# pca10040_sheet4_connectors.net
KiCad netlist of a schematic drawn in Altium Designer
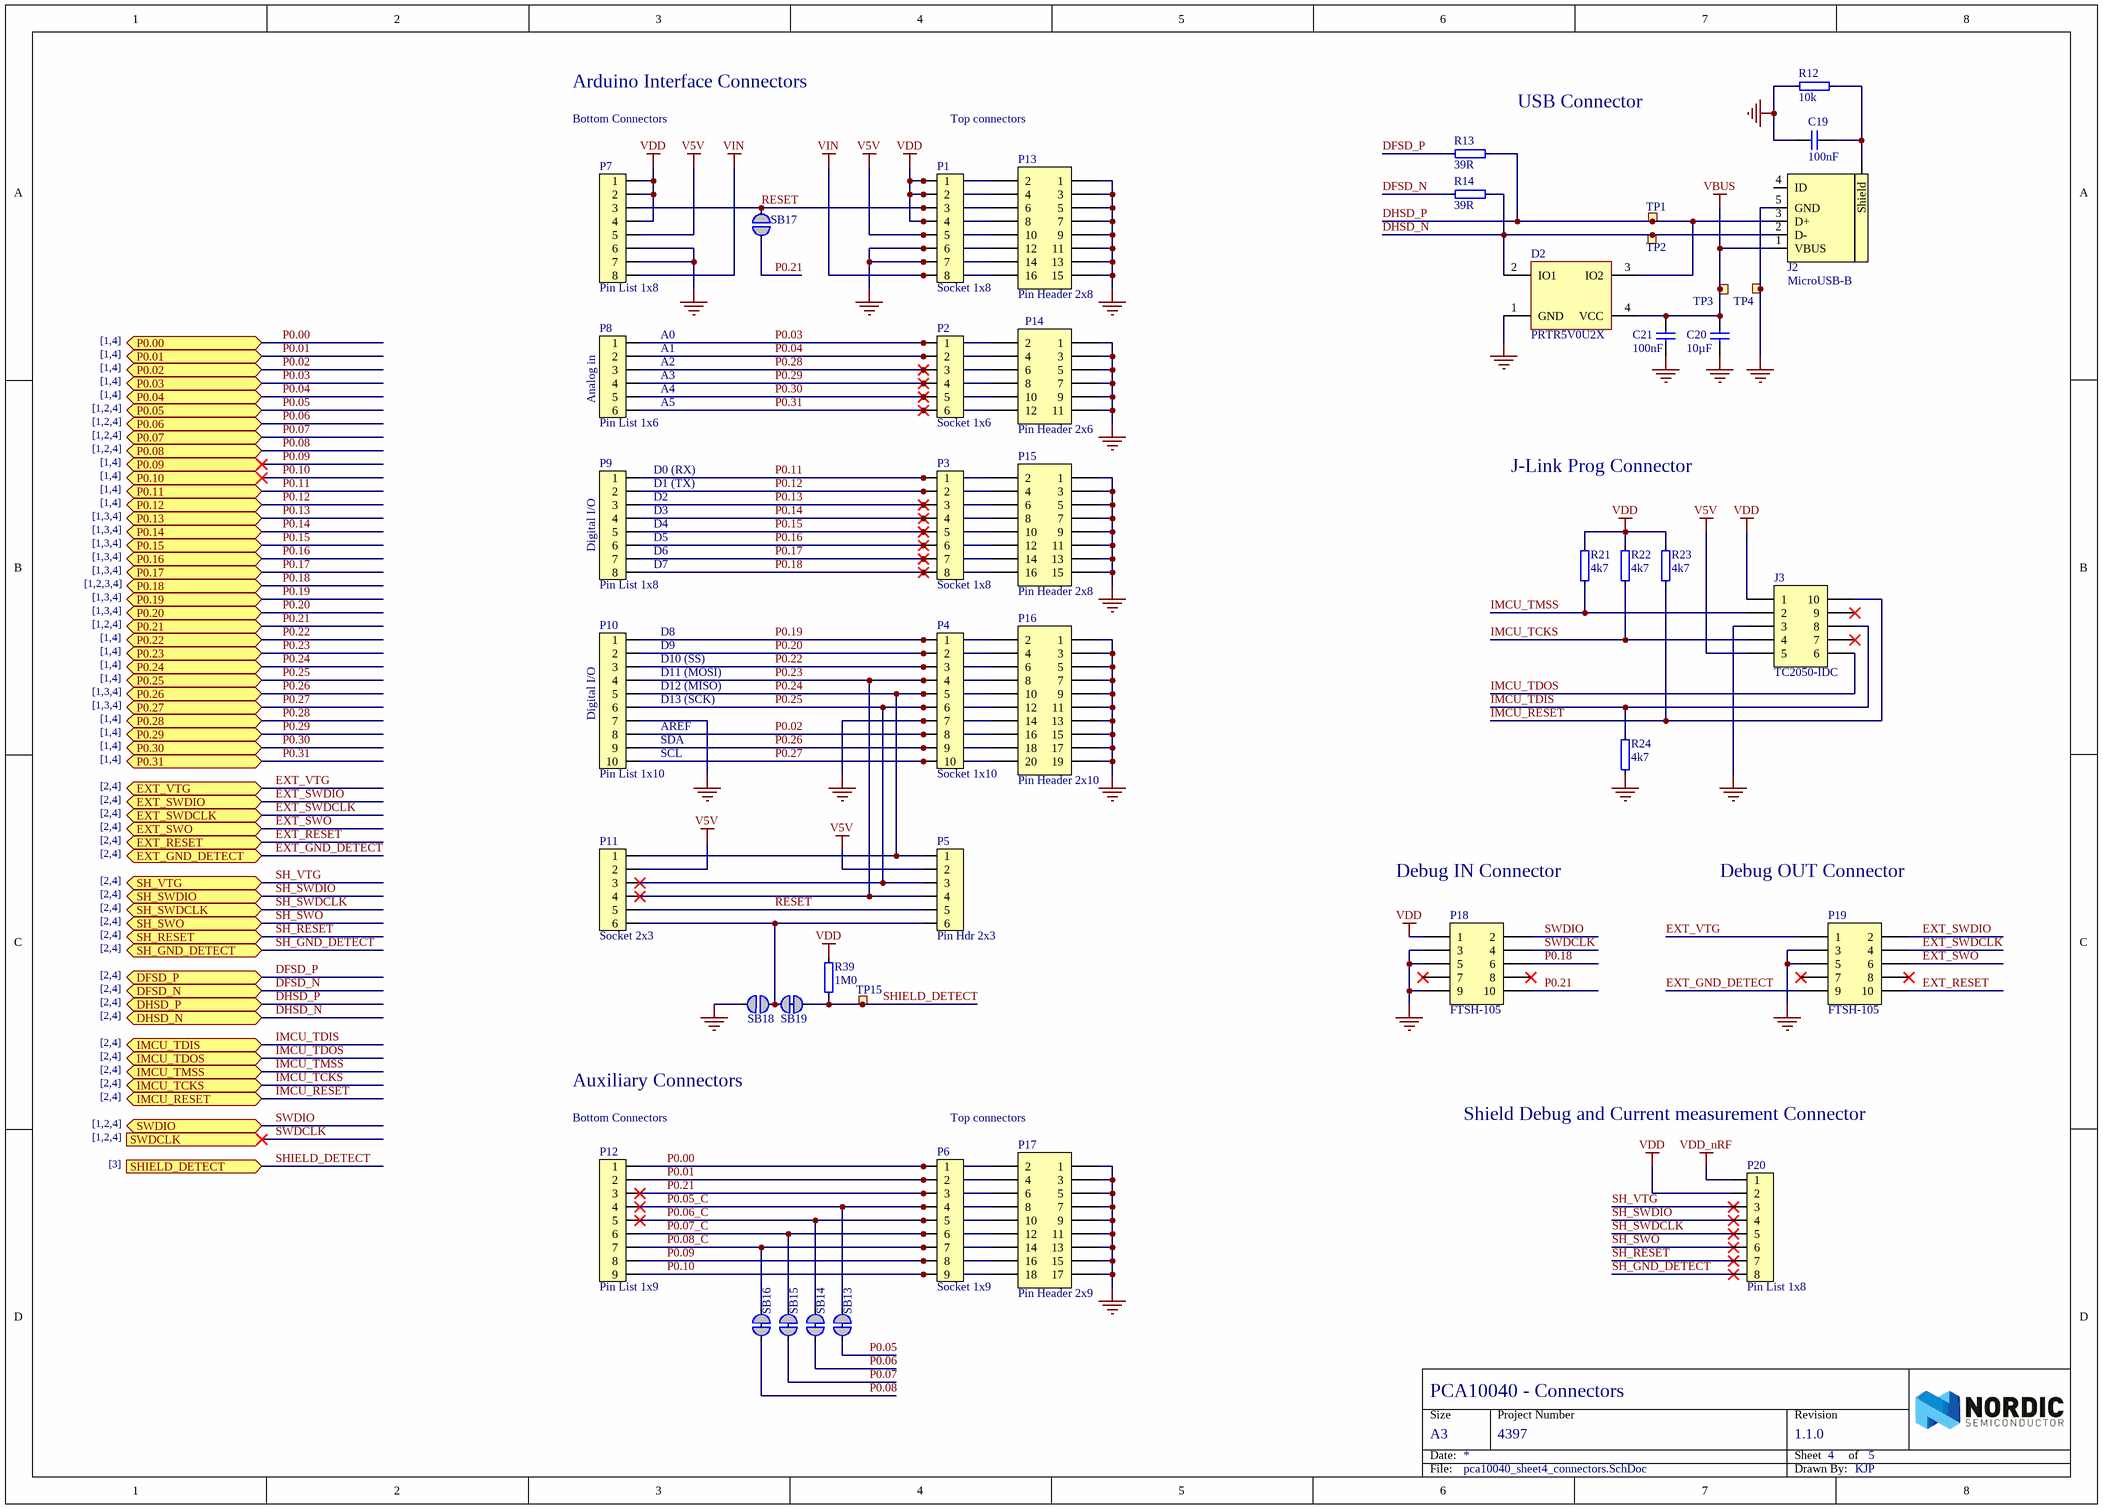
[diagram p0: pca10040_sheet4_connectors.SchDoc]

(export (version "E")
  (design (tool "Eeschema 10.0.6"))
  (components
    (comp (ref "C19")
      (value "100nF")
      (footprint "CAPC1005X04L")
      (description "Capacitor, X7R, ±10%")
      (fields (field (name "PART NUMBER") "C0402-100n") (field (name "PUBLISHER") "Nordic Semiconductor"))
      (libsource (lib "Nordic Passive DB") (part "CAP"))
    )
    (comp (ref "C20")
      (value "10µF")
      (footprint "CAPC1608X06L")
      (description "Capacitor, X5R, ±20%")
      (fields (field (name "PART NUMBER") "C0603-10µ") (field (name "PUBLISHER") "Nordic Semiconductor"))
      (libsource (lib "Nordic Passive DB") (part "CAP"))
    )
    (comp (ref "C21")
      (value "100nF")
      (footprint "CAPC1005X04L")
      (description "Capacitor, X7R, ±10%")
      (fields (field (name "PART NUMBER") "C0402-100n") (field (name "PUBLISHER") "Nordic Semiconductor"))
      (libsource (lib "Nordic Passive DB") (part "CAP"))
    )
    (comp (ref "D2")
      (value "PRTR5V0U2X")
      (footprint "SOT190P230X110-4L")
      (description "Ultra low capacitance double rail-to-rail ESD protection diode")
      (fields
        (field (name "MANUFACTURER") "NXP")
        (field (name "2ND SOURCE PART NUMBER") "152-4157")
        (field (name "PUBLISHER") "Nordic Semiconductor")
      )
      (libsource (lib "Nordic Discrete DB") (part "PRTR5V0U2X"))
    )
    (comp (ref "J2")
      (value "MicroUSB-B")
      (footprint "FCI_10118193-0001LF")
      (description "MicroUSB-B-SMT")
      (fields
        (field (name "PART NUMBER") "FCI 10118193-0001LF")
        (field (name "MANUFACTURER") "FCI")
        (field (name "PUBLISHER") "Nordic Semiconductor")
      )
      (libsource (lib "Nordic Passive DB") (part "MiniUSB-AB-SMT"))
    )
    (comp (ref "J3")
      (value "TC2050-IDC")
      (footprint "TC2050-IDC-NLFP")
      (description "CBL PLUG-OF-NAILS 10-PIN")
      (fields
        (field (name "PART NUMBER") "TC2050-IDC-NLFP")
        (field (name "MANUFACTURER") "Tag-Connect LLC")
        (field (name "PUBLISHER") "Nordic Semiconductor")
      )
      (libsource (lib "Nordic Passive DB") (part "CONN-2x5_var2"))
    )
    (comp (ref "P1")
      (value "Socket 1x8")
      (footprint "SOCKET_1x8_SMD")
      (description "Socket 1x8, 2.54mm (100mil), SMD")
      (fields
        (field (name "PART NUMBER") "Socket 1x8 SMD")
        (field (name "MANUFACTURER") "Cabcon")
        (field (name "PUBLISHER") "Nordic Semiconductor")
      )
      (libsource (lib "Nordic Passive DB") (part "CONN-8"))
    )
    (comp (ref "P2")
      (value "Socket 1x6")
      (footprint "SOCKET_1x6_SMD")
      (description "Socket 1x6, 2.54mm (100mil), SMD")
      (fields
        (field (name "PART NUMBER") "Socket 1x6 SMD")
        (field (name "MANUFACTURER") "Cabcon")
        (field (name "PUBLISHER") "Nordic Semiconductor")
      )
      (libsource (lib "Nordic Passive DB") (part "CONN-6"))
    )
    (comp (ref "P3")
      (value "Socket 1x8")
      (footprint "SOCKET_1x8_SMD")
      (description "Socket 1x8, 2.54mm (100mil), SMD")
      (fields
        (field (name "PART NUMBER") "Socket 1x8 SMD")
        (field (name "MANUFACTURER") "Cabcon")
        (field (name "PUBLISHER") "Nordic Semiconductor")
      )
      (libsource (lib "Nordic Passive DB") (part "CONN-8"))
    )
    (comp (ref "P4")
      (value "Socket 1x10")
      (footprint "SOCKET_1x10_SMD")
      (description "Socket 1x10, 2.54mm (100mil), SMD")
      (fields
        (field (name "PART NUMBER") "Socket 1x10 SMD")
        (field (name "MANUFACTURER") "Cabcon")
        (field (name "PUBLISHER") "Nordic Semiconductor")
      )
      (libsource (lib "Nordic Passive DB") (part "CONN-10"))
    )
    (comp (ref "P5")
      (value "Pin Hdr 2x3")
      (footprint "Molex 15-91-2060")
      (description "Pin Header 2x3, 2.54mm (100mil) SMD")
      (fields
        (field (name "PART NUMBER") "Pin Header 2x3 SMD")
        (field (name "MANUFACTURER") "Cabcon")
        (field (name "PUBLISHER") "Nordic Semiconductor")
      )
      (libsource (lib "Nordic Passive DB") (part "CONN-6"))
    )
    (comp (ref "P6")
      (value "Socket 1x9")
      (footprint "SOCKET_1x9_SMD")
      (description "Socket 1x9, 2.54mm (100mil), SMD")
      (fields
        (field (name "PART NUMBER") "Socket 1x9 SMD")
        (field (name "MANUFACTURER") "Cabcon")
        (field (name "PUBLISHER") "Nordic Semiconductor")
      )
      (libsource (lib "Nordic Passive DB") (part "CONN-9"))
    )
    (comp (ref "P7")
      (value "Pin List 1x8")
      (footprint "LIST_1x8_SMD")
      (description "Pin List 1x8, 2.54mm (100mil), SMD")
      (fields
        (field (name "PART NUMBER") "Pin List 1x8 SMD")
        (field (name "PUBLISHER") "Nordic Semiconductor")
      )
      (libsource (lib "") (part "CONN-8_1"))
    )
    (comp (ref "P8")
      (value "Pin List 1x6")
      (footprint "LIST_1x6_SMD")
      (description "Pin List 1x6, 2.54mm (100mil), SMD")
      (fields
        (field (name "PART NUMBER") "Pin List 1x6 SMD")
        (field (name "PUBLISHER") "Nordic Semiconductor")
      )
      (libsource (lib "") (part "CONN-6_1"))
    )
    (comp (ref "P9")
      (value "Pin List 1x8")
      (footprint "LIST_1x8_SMD")
      (description "Pin List 1x8, 2.54mm (100mil), SMD")
      (fields
        (field (name "PART NUMBER") "Pin List 1x8 SMD")
        (field (name "PUBLISHER") "Nordic Semiconductor")
      )
      (libsource (lib "") (part "CONN-8_1"))
    )
    (comp (ref "P10")
      (value "Pin List 1x10")
      (footprint "LIST_1x10_SMD")
      (description "Pin List 1x10, 2.54mm (100mil), SMD")
      (fields
        (field (name "PART NUMBER") "Pin List 1x10 SMD")
        (field (name "PUBLISHER") "Nordic Semiconductor")
      )
      (libsource (lib "") (part "CONN-10_1"))
    )
    (comp (ref "P11")
      (value "Socket 2x3")
      (footprint "SOCKET_2x3_SMD-2.54mm-bottom")
      (description "Socket 2x3, 2.54mm (100mil), SMD")
      (fields
        (field (name "PART NUMBER") "Socket 2x3 SMD Bottom")
        (field (name "MANUFACTURER") "Samtec")
        (field (name "PUBLISHER") "Nordic Semiconductor")
      )
      (libsource (lib "") (part "CONN-6_1"))
    )
    (comp (ref "P12")
      (value "Pin List 1x9")
      (footprint "LIST_1x9_SMD")
      (description "Pin List 1x9, 2.54mm (100mil), SMD")
      (fields
        (field (name "PART NUMBER") "Pin List 1x9 SMD")
        (field (name "PUBLISHER") "Nordic Semiconductor")
      )
      (libsource (lib "") (part "CONN-9_1"))
    )
    (comp (ref "P13")
      (value "Pin Header 2x8")
      (footprint "HDR_2x8")
      (description "Pin Header 2x8, 2.54mm (100mil)")
      (fields (field (name "PUBLISHER") "Nordic Semiconductor"))
      (libsource (lib "Nordic Passive DB") (part "CONN-2x8"))
    )
    (comp (ref "P14")
      (value "Pin Header 2x6")
      (footprint "HDR_2x6")
      (description "Pin Header 2x6, 2.54mm (100mil)")
      (fields (field (name "PUBLISHER") "Nordic Semiconductor"))
      (libsource (lib "Nordic Passive DB") (part "CONN-2x6"))
    )
    (comp (ref "P15")
      (value "Pin Header 2x8")
      (footprint "HDR_2x8")
      (description "Pin Header 2x8, 2.54mm (100mil)")
      (fields (field (name "PUBLISHER") "Nordic Semiconductor"))
      (libsource (lib "Nordic Passive DB") (part "CONN-2x8"))
    )
    (comp (ref "P16")
      (value "Pin Header 2x10")
      (footprint "HDR_2x10")
      (description "Pin Header 2x10, 2.54mm (100mil)")
      (fields (field (name "PUBLISHER") "Nordic Semiconductor"))
      (libsource (lib "Nordic Passive DB") (part "CONN-2x10"))
    )
    (comp (ref "P17")
      (value "Pin Header 2x9")
      (footprint "HDR_2x9")
      (description "Pin Header 2x9, 2.54mm (100mil)")
      (fields (field (name "PUBLISHER") "Nordic Semiconductor"))
      (libsource (lib "Nordic Passive DB") (part "CONN-2x9"))
    )
    (comp (ref "P18")
      (value "FTSH-105")
      (footprint "FTSH-105-K")
      (description "CONN HEADER 10POS DUAL .05\" SMD KEYING SHROUD")
      (fields
        (field (name "PART NUMBER") "Samtec FTSH-105 Keying Shroud")
        (field (name "MANUFACTURER") "Cabcon")
        (field (name "PUBLISHER") "Nordic Semiconductor")
      )
      (libsource (lib "Nordic Passive DB") (part "CONN-2x5"))
    )
    (comp (ref "P19")
      (value "FTSH-105")
      (footprint "FTSH-105-K")
      (description "CONN HEADER 10POS DUAL .05\" SMD KEYING SHROUD")
      (fields
        (field (name "PART NUMBER") "Samtec FTSH-105 Keying Shroud")
        (field (name "MANUFACTURER") "Cabcon")
        (field (name "PUBLISHER") "Nordic Semiconductor")
      )
      (libsource (lib "Nordic Passive DB") (part "CONN-2x5"))
    )
    (comp (ref "P20")
      (value "Pin List 1x8")
      (footprint "LIST_1x8_SMD")
      (description "Pin List 1x8, 2.54mm (100mil), SMD")
      (fields
        (field (name "PART NUMBER") "Pin List 1x8 SMD")
        (field (name "MANUFACTURER") "Cabcon")
        (field (name "PUBLISHER") "Nordic Semiconductor")
      )
      (libsource (lib "Nordic Passive DB") (part "CONN-8"))
    )
    (comp (ref "R12")
      (value "10k")
      (footprint "RESC1005X04L")
      (description "Resistor, ±1%, 0.063W")
      (fields (field (name "PART NUMBER") "R0402-10k") (field (name "PUBLISHER") "Nordic Semiconductor"))
      (libsource (lib "Nordic Passive DB") (part "RES_1"))
    )
    (comp (ref "R13")
      (value "39R")
      (footprint "RESC1005X04L")
      (description "Resistor, ±1%, 0.063W")
      (fields (field (name "PART NUMBER") "R0402-39R") (field (name "PUBLISHER") "Nordic Semiconductor"))
      (libsource (lib "Nordic Passive DB") (part "RES_1"))
    )
    (comp (ref "R14")
      (value "39R")
      (footprint "RESC1005X04L")
      (description "Resistor, ±1%, 0.063W")
      (fields (field (name "PART NUMBER") "R0402-39R") (field (name "PUBLISHER") "Nordic Semiconductor"))
      (libsource (lib "Nordic Passive DB") (part "RES_1"))
    )
    (comp (ref "R21")
      (value "4k7")
      (footprint "RESC1005X04L")
      (description "Resistor, ±1%, 0.063W")
      (fields (field (name "PART NUMBER") "R0402-4k7") (field (name "PUBLISHER") "Nordic Semiconductor"))
      (libsource (lib "Nordic Passive DB") (part "RES_1"))
    )
    (comp (ref "R22")
      (value "4k7")
      (footprint "RESC1005X04L")
      (description "Resistor, ±1%, 0.063W")
      (fields (field (name "PART NUMBER") "R0402-4k7") (field (name "PUBLISHER") "Nordic Semiconductor"))
      (libsource (lib "Nordic Passive DB") (part "RES_1"))
    )
    (comp (ref "R23")
      (value "4k7")
      (footprint "RESC1005X04L")
      (description "Resistor, ±1%, 0.063W")
      (fields (field (name "PART NUMBER") "R0402-4k7") (field (name "PUBLISHER") "Nordic Semiconductor"))
      (libsource (lib "Nordic Passive DB") (part "RES_1"))
    )
    (comp (ref "R24")
      (value "4k7")
      (footprint "RESC1005X04L")
      (description "Resistor, ±1%, 0.063W")
      (fields (field (name "PART NUMBER") "R0402-4k7") (field (name "PUBLISHER") "Nordic Semiconductor"))
      (libsource (lib "Nordic Passive DB") (part "RES_1"))
    )
    (comp (ref "R39")
      (value "1M0")
      (footprint "RESC1005X04L")
      (description "Resistor, ±1%, 0.063W")
      (fields (field (name "PART NUMBER") "R0402-1M0") (field (name "PUBLISHER") "Nordic Semiconductor"))
      (libsource (lib "Nordic Passive DB") (part "RES_1"))
    )
    (comp (ref "SB13")
      (value "Solderbridge")
      (footprint "Solderbridge_Shorted")
      (description "Shorted Solderbridge")
      (fields
        (field (name "PART NUMBER") "Solderbridge Shorted")
        (field (name "PUBLISHER") "Nordic Semiconductor")
      )
      (libsource (lib "Nordic Passive DB") (part "SOLDERBRIDGE_SHORTED"))
    )
    (comp (ref "SB14")
      (value "Solderbridge")
      (footprint "Solderbridge_Shorted")
      (description "Shorted Solderbridge")
      (fields
        (field (name "PART NUMBER") "Solderbridge Shorted")
        (field (name "PUBLISHER") "Nordic Semiconductor")
      )
      (libsource (lib "Nordic Passive DB") (part "SOLDERBRIDGE_SHORTED"))
    )
    (comp (ref "SB15")
      (value "Solderbridge")
      (footprint "Solderbridge_Shorted")
      (description "Shorted Solderbridge")
      (fields
        (field (name "PART NUMBER") "Solderbridge Shorted")
        (field (name "PUBLISHER") "Nordic Semiconductor")
      )
      (libsource (lib "Nordic Passive DB") (part "SOLDERBRIDGE_SHORTED"))
    )
    (comp (ref "SB16")
      (value "Solderbridge")
      (footprint "Solderbridge_Shorted")
      (description "Shorted Solderbridge")
      (fields
        (field (name "PART NUMBER") "Solderbridge Shorted")
        (field (name "PUBLISHER") "Nordic Semiconductor")
      )
      (libsource (lib "Nordic Passive DB") (part "SOLDERBRIDGE_SHORTED"))
    )
    (comp (ref "SB17")
      (value "Solderbridge")
      (footprint "Solderbridge")
      (fields (field (name "PUBLISHER") "Nordic Semiconductor"))
      (libsource (lib "Nordic Passive DB") (part "SOLDERBRIDGE"))
    )
    (comp (ref "SB18")
      (value "Solderbridge")
      (footprint "Solderbridge")
      (fields (field (name "PUBLISHER") "Nordic Semiconductor"))
      (libsource (lib "Nordic Passive DB") (part "SOLDERBRIDGE"))
    )
    (comp (ref "SB19")
      (value "Solderbridge")
      (footprint "Solderbridge_Shorted")
      (description "Shorted Solderbridge")
      (fields
        (field (name "PART NUMBER") "Solderbridge Shorted")
        (field (name "PUBLISHER") "Nordic Semiconductor")
      )
      (libsource (lib "Nordic Passive DB") (part "SOLDERBRIDGE_SHORTED"))
    )
    (comp (ref "TP1")
      (value "Ø1.0mm,SMD")
      (footprint "TP_SMD_Ø1.0mm")
      (description "1.0mm circular SMD testpad")
      (fields
        (field (name "PART NUMBER") "TP_SMD_Ø1.0MM")
        (field (name "MANUFACTURER") "Nordic Semiconductor")
        (field (name "PUBLISHER") "Nordic Semiconductor")
      )
      (libsource (lib "") (part "TESTPAD_2"))
    )
    (comp (ref "TP2")
      (value "Ø1.0mm,SMD")
      (footprint "TP_SMD_Ø1.0mm")
      (description "1.0mm circular SMD testpad")
      (fields
        (field (name "PART NUMBER") "TP_SMD_Ø1.0MM")
        (field (name "MANUFACTURER") "Nordic Semiconductor")
        (field (name "PUBLISHER") "Nordic Semiconductor")
      )
      (libsource (lib "") (part "TESTPAD_1"))
    )
    (comp (ref "TP3")
      (value "Ø1.0mm,SMD")
      (footprint "TP_SMD_Ø1.0mm")
      (description "1.0mm circular SMD testpad")
      (fields
        (field (name "PART NUMBER") "TP_SMD_Ø1.0MM")
        (field (name "MANUFACTURER") "Nordic Semiconductor")
        (field (name "PUBLISHER") "Nordic Semiconductor")
      )
      (libsource (lib "") (part "TESTPAD_3"))
    )
    (comp (ref "TP4")
      (value "Ø1.0mm,SMD")
      (footprint "TP_SMD_Ø1.0mm")
      (description "1.0mm circular SMD testpad")
      (fields
        (field (name "PART NUMBER") "TP_SMD_Ø1.0MM")
        (field (name "MANUFACTURER") "Nordic Semiconductor")
        (field (name "PUBLISHER") "Nordic Semiconductor")
      )
      (libsource (lib "Nordic Passive DB") (part "TESTPAD"))
    )
    (comp (ref "TP15")
      (value "Ø1.0mm,SMD")
      (footprint "TP_SMD_Ø1.0mm")
      (description "1.0mm circular SMD testpad")
      (fields
        (field (name "PART NUMBER") "TP_SMD_Ø1.0MM")
        (field (name "MANUFACTURER") "Nordic Semiconductor")
        (field (name "PUBLISHER") "Nordic Semiconductor")
      )
      (libsource (lib "") (part "TESTPAD_2"))
    )
  )
  (nets
    (net (code "1") (name "/DFSD_N") (class "Default")
      (node (ref "R14") (pin "1") (pinfunction "1_1") (pintype "passive"))
    )
    (net (code "2") (name "/DFSD_P") (class "Default")
      (node (ref "R13") (pin "1") (pinfunction "1_1") (pintype "passive"))
    )
    (net (code "3") (name "/DHSD_N") (class "Default")
      (node (ref "D2") (pin "2") (pinfunction "IO1_2") (pintype "passive"))
      (node (ref "J2") (pin "2") (pinfunction "D-_2") (pintype "passive"))
      (node (ref "R14") (pin "2") (pinfunction "2_2") (pintype "passive"))
      (node (ref "TP2") (pin "1") (pinfunction "1_1") (pintype "passive"))
    )
    (net (code "4") (name "/DHSD_P") (class "Default")
      (node (ref "D2") (pin "3") (pinfunction "IO2_3") (pintype "passive"))
      (node (ref "J2") (pin "3") (pinfunction "D+_3") (pintype "passive"))
      (node (ref "R13") (pin "2") (pinfunction "2_2") (pintype "passive"))
      (node (ref "TP1") (pin "1") (pinfunction "1_1") (pintype "passive"))
    )
    (net (code "5") (name "/EXT_GND_DETECT") (class "Default")
      (node (ref "P19") (pin "9") (pinfunction "9_9") (pintype "passive"))
    )
    (net (code "6") (name "/EXT_RESET") (class "Default")
      (node (ref "P19") (pin "10") (pinfunction "10_10") (pintype "passive"))
    )
    (net (code "7") (name "/EXT_SWDCLK") (class "Default")
      (node (ref "P19") (pin "4") (pinfunction "4_4") (pintype "passive"))
    )
    (net (code "8") (name "/EXT_SWDIO") (class "Default")
      (node (ref "P19") (pin "2") (pinfunction "2_2") (pintype "passive"))
    )
    (net (code "9") (name "/EXT_SWO") (class "Default")
      (node (ref "P19") (pin "6") (pinfunction "6_6") (pintype "passive"))
    )
    (net (code "10") (name "/EXT_VTG") (class "Default")
      (node (ref "P19") (pin "1") (pinfunction "1_1") (pintype "passive"))
    )
    (net (code "11") (name "/IMCU_RESET") (class "Default")
      (node (ref "J3") (pin "10") (pinfunction "10_10") (pintype "passive"))
      (node (ref "R23") (pin "1") (pinfunction "1_1") (pintype "passive"))
    )
    (net (code "12") (name "/IMCU_TCKS") (class "Default")
      (node (ref "J3") (pin "4") (pinfunction "4_4") (pintype "passive"))
      (node (ref "R22") (pin "1") (pinfunction "1_1") (pintype "passive"))
    )
    (net (code "13") (name "/IMCU_TDIS") (class "Default")
      (node (ref "J3") (pin "8") (pinfunction "8_8") (pintype "passive"))
      (node (ref "R24") (pin "1") (pinfunction "1_1") (pintype "passive"))
    )
    (net (code "14") (name "/IMCU_TDOS") (class "Default")
      (node (ref "J3") (pin "6") (pinfunction "6_6") (pintype "passive"))
    )
    (net (code "15") (name "/IMCU_TMSS") (class "Default")
      (node (ref "J3") (pin "2") (pinfunction "2_2") (pintype "passive"))
      (node (ref "R21") (pin "1") (pinfunction "1_1") (pintype "passive"))
    )
    (net (code "16") (name "/P0.00") (class "Default")
      (node (ref "P12") (pin "1") (pinfunction "1_1") (pintype "passive"))
      (node (ref "P17") (pin "2") (pinfunction "2_2") (pintype "passive"))
      (node (ref "P6") (pin "1") (pinfunction "1_1") (pintype "passive"))
    )
    (net (code "17") (name "/P0.01") (class "Default")
      (node (ref "P12") (pin "2") (pinfunction "2_2") (pintype "passive"))
      (node (ref "P17") (pin "4") (pinfunction "4_4") (pintype "passive"))
      (node (ref "P6") (pin "2") (pinfunction "2_2") (pintype "passive"))
    )
    (net (code "18") (name "/P0.02") (class "Default")
      (node (ref "P10") (pin "8") (pinfunction "8_8") (pintype "passive"))
      (node (ref "P16") (pin "16") (pinfunction "16_16") (pintype "passive"))
      (node (ref "P4") (pin "8") (pinfunction "8_8") (pintype "passive"))
    )
    (net (code "19") (name "/P0.03") (class "Default")
      (node (ref "P14") (pin "2") (pinfunction "2_2") (pintype "passive"))
      (node (ref "P2") (pin "1") (pinfunction "1_1") (pintype "passive"))
      (node (ref "P8") (pin "1") (pinfunction "1_1") (pintype "passive"))
    )
    (net (code "20") (name "/P0.04") (class "Default")
      (node (ref "P14") (pin "4") (pinfunction "4_4") (pintype "passive"))
      (node (ref "P2") (pin "2") (pinfunction "2_2") (pintype "passive"))
      (node (ref "P8") (pin "2") (pinfunction "2_2") (pintype "passive"))
    )
    (net (code "21") (name "/P0.05") (class "Default")
      (node (ref "SB13") (pin "2") (pinfunction "1_2") (pintype "passive"))
    )
    (net (code "22") (name "/P0.05_C") (class "Default")
      (node (ref "P12") (pin "4") (pinfunction "4_4") (pintype "power_in"))
      (node (ref "P17") (pin "8") (pinfunction "8_8") (pintype "passive"))
      (node (ref "P6") (pin "4") (pinfunction "4_4") (pintype "power_in"))
      (node (ref "SB13") (pin "1") (pinfunction "0_1") (pintype "passive"))
    )
    (net (code "23") (name "/P0.06") (class "Default")
      (node (ref "SB14") (pin "2") (pinfunction "1_2") (pintype "passive"))
    )
    (net (code "24") (name "/P0.06_C") (class "Default")
      (node (ref "P12") (pin "5") (pinfunction "5_5") (pintype "power_in"))
      (node (ref "P17") (pin "10") (pinfunction "10_10") (pintype "passive"))
      (node (ref "P6") (pin "5") (pinfunction "5_5") (pintype "power_in"))
      (node (ref "SB14") (pin "1") (pinfunction "0_1") (pintype "passive"))
    )
    (net (code "25") (name "/P0.07") (class "Default")
      (node (ref "SB15") (pin "2") (pinfunction "1_2") (pintype "passive"))
    )
    (net (code "26") (name "/P0.07_C") (class "Default")
      (node (ref "P12") (pin "6") (pinfunction "6_6") (pintype "power_in"))
      (node (ref "P17") (pin "12") (pinfunction "12_12") (pintype "passive"))
      (node (ref "P6") (pin "6") (pinfunction "6_6") (pintype "power_in"))
      (node (ref "SB15") (pin "1") (pinfunction "0_1") (pintype "passive"))
    )
    (net (code "27") (name "/P0.08") (class "Default")
      (node (ref "SB16") (pin "2") (pinfunction "1_2") (pintype "passive"))
    )
    (net (code "28") (name "/P0.08_C") (class "Default")
      (node (ref "P12") (pin "7") (pinfunction "7_7") (pintype "power_in"))
      (node (ref "P17") (pin "14") (pinfunction "14_14") (pintype "passive"))
      (node (ref "P6") (pin "7") (pinfunction "7_7") (pintype "power_in"))
      (node (ref "SB16") (pin "1") (pinfunction "0_1") (pintype "passive"))
    )
    (net (code "29") (name "/P0.09") (class "Default")
      (node (ref "P12") (pin "8") (pinfunction "8_8") (pintype "power_in"))
      (node (ref "P17") (pin "16") (pinfunction "16_16") (pintype "passive"))
      (node (ref "P6") (pin "8") (pinfunction "8_8") (pintype "power_in"))
    )
    (net (code "30") (name "/P0.10") (class "Default")
      (node (ref "P12") (pin "9") (pinfunction "9_9") (pintype "power_in"))
      (node (ref "P17") (pin "18") (pinfunction "18_18") (pintype "passive"))
      (node (ref "P6") (pin "9") (pinfunction "9_9") (pintype "power_in"))
    )
    (net (code "31") (name "/P0.11") (class "Default")
      (node (ref "P15") (pin "2") (pinfunction "2_2") (pintype "passive"))
      (node (ref "P3") (pin "1") (pinfunction "1_1") (pintype "passive"))
      (node (ref "P9") (pin "1") (pinfunction "1_1") (pintype "passive"))
    )
    (net (code "32") (name "/P0.12") (class "Default")
      (node (ref "P15") (pin "4") (pinfunction "4_4") (pintype "passive"))
      (node (ref "P3") (pin "2") (pinfunction "2_2") (pintype "passive"))
      (node (ref "P9") (pin "2") (pinfunction "2_2") (pintype "passive"))
    )
    (net (code "33") (name "/P0.13") (class "Default")
      (node (ref "P15") (pin "6") (pinfunction "6_6") (pintype "passive"))
      (node (ref "P3") (pin "3") (pinfunction "3_3") (pintype "passive"))
      (node (ref "P9") (pin "3") (pinfunction "3_3") (pintype "power_in"))
    )
    (net (code "34") (name "/P0.14") (class "Default")
      (node (ref "P15") (pin "8") (pinfunction "8_8") (pintype "passive"))
      (node (ref "P3") (pin "4") (pinfunction "4_4") (pintype "passive"))
      (node (ref "P9") (pin "4") (pinfunction "4_4") (pintype "power_in"))
    )
    (net (code "35") (name "/P0.15") (class "Default")
      (node (ref "P15") (pin "10") (pinfunction "10_10") (pintype "passive"))
      (node (ref "P3") (pin "5") (pinfunction "5_5") (pintype "passive"))
      (node (ref "P9") (pin "5") (pinfunction "5_5") (pintype "power_in"))
    )
    (net (code "36") (name "/P0.16") (class "Default")
      (node (ref "P15") (pin "12") (pinfunction "12_12") (pintype "passive"))
      (node (ref "P3") (pin "6") (pinfunction "6_6") (pintype "passive"))
      (node (ref "P9") (pin "6") (pinfunction "6_6") (pintype "power_in"))
    )
    (net (code "37") (name "/P0.17") (class "Default")
      (node (ref "P15") (pin "14") (pinfunction "14_14") (pintype "passive"))
      (node (ref "P3") (pin "7") (pinfunction "7_7") (pintype "passive"))
      (node (ref "P9") (pin "7") (pinfunction "7_7") (pintype "power_in"))
    )
    (net (code "38") (name "/P0.18") (class "Default")
      (node (ref "P15") (pin "16") (pinfunction "16_16") (pintype "passive"))
      (node (ref "P18") (pin "6") (pinfunction "6_6") (pintype "passive"))
      (node (ref "P3") (pin "8") (pinfunction "8_8") (pintype "passive"))
      (node (ref "P9") (pin "8") (pinfunction "8_8") (pintype "power_in"))
    )
    (net (code "39") (name "/P0.19") (class "Default")
      (node (ref "P10") (pin "1") (pinfunction "1_1") (pintype "passive"))
      (node (ref "P16") (pin "2") (pinfunction "2_2") (pintype "passive"))
      (node (ref "P4") (pin "1") (pinfunction "1_1") (pintype "passive"))
    )
    (net (code "40") (name "/P0.20") (class "Default")
      (node (ref "P10") (pin "2") (pinfunction "2_2") (pintype "passive"))
      (node (ref "P16") (pin "4") (pinfunction "4_4") (pintype "passive"))
      (node (ref "P4") (pin "2") (pinfunction "2_2") (pintype "passive"))
    )
    (net (code "41") (name "/P0.21") (class "Default")
      (node (ref "P12") (pin "3") (pinfunction "3_3") (pintype "power_in"))
      (node (ref "P17") (pin "6") (pinfunction "6_6") (pintype "passive"))
      (node (ref "P18") (pin "10") (pinfunction "10_10") (pintype "passive"))
      (node (ref "P6") (pin "3") (pinfunction "3_3") (pintype "power_in"))
      (node (ref "SB17") (pin "2") (pinfunction "1_2") (pintype "passive"))
    )
    (net (code "42") (name "/P0.22") (class "Default")
      (node (ref "P10") (pin "3") (pinfunction "3_3") (pintype "passive"))
      (node (ref "P16") (pin "6") (pinfunction "6_6") (pintype "passive"))
      (node (ref "P4") (pin "3") (pinfunction "3_3") (pintype "passive"))
    )
    (net (code "43") (name "/P0.23") (class "Default")
      (node (ref "P10") (pin "4") (pinfunction "4_4") (pintype "passive"))
      (node (ref "P11") (pin "4") (pinfunction "4_4") (pintype "power_in"))
      (node (ref "P16") (pin "8") (pinfunction "8_8") (pintype "passive"))
      (node (ref "P4") (pin "4") (pinfunction "4_4") (pintype "passive"))
      (node (ref "P5") (pin "4") (pinfunction "4_4") (pintype "passive"))
    )
    (net (code "44") (name "/P0.24") (class "Default")
      (node (ref "P10") (pin "5") (pinfunction "5_5") (pintype "passive"))
      (node (ref "P11") (pin "1") (pinfunction "1_1") (pintype "passive"))
      (node (ref "P16") (pin "10") (pinfunction "10_10") (pintype "passive"))
      (node (ref "P4") (pin "5") (pinfunction "5_5") (pintype "passive"))
      (node (ref "P5") (pin "1") (pinfunction "1_1") (pintype "passive"))
    )
    (net (code "45") (name "/P0.25") (class "Default")
      (node (ref "P10") (pin "6") (pinfunction "6_6") (pintype "passive"))
      (node (ref "P11") (pin "3") (pinfunction "3_3") (pintype "power_in"))
      (node (ref "P16") (pin "12") (pinfunction "12_12") (pintype "passive"))
      (node (ref "P4") (pin "6") (pinfunction "6_6") (pintype "passive"))
      (node (ref "P5") (pin "3") (pinfunction "3_3") (pintype "passive"))
    )
    (net (code "46") (name "/P0.26") (class "Default")
      (node (ref "P10") (pin "9") (pinfunction "9_9") (pintype "passive"))
      (node (ref "P16") (pin "18") (pinfunction "18_18") (pintype "passive"))
      (node (ref "P4") (pin "9") (pinfunction "9_9") (pintype "passive"))
    )
    (net (code "47") (name "/P0.27") (class "Default")
      (node (ref "P10") (pin "10") (pinfunction "10_10") (pintype "passive"))
      (node (ref "P16") (pin "20") (pinfunction "20_20") (pintype "passive"))
      (node (ref "P4") (pin "10") (pinfunction "10_10") (pintype "passive"))
    )
    (net (code "48") (name "/P0.28") (class "Default")
      (node (ref "P14") (pin "6") (pinfunction "6_6") (pintype "passive"))
      (node (ref "P2") (pin "3") (pinfunction "3_3") (pintype "passive"))
      (node (ref "P8") (pin "3") (pinfunction "3_3") (pintype "power_in"))
    )
    (net (code "49") (name "/P0.29") (class "Default")
      (node (ref "P14") (pin "8") (pinfunction "8_8") (pintype "passive"))
      (node (ref "P2") (pin "4") (pinfunction "4_4") (pintype "passive"))
      (node (ref "P8") (pin "4") (pinfunction "4_4") (pintype "power_in"))
    )
    (net (code "50") (name "/P0.30") (class "Default")
      (node (ref "P14") (pin "10") (pinfunction "10_10") (pintype "passive"))
      (node (ref "P2") (pin "5") (pinfunction "5_5") (pintype "passive"))
      (node (ref "P8") (pin "5") (pinfunction "5_5") (pintype "power_in"))
    )
    (net (code "51") (name "/P0.31") (class "Default")
      (node (ref "P14") (pin "12") (pinfunction "12_12") (pintype "passive"))
      (node (ref "P2") (pin "6") (pinfunction "6_6") (pintype "passive"))
      (node (ref "P8") (pin "6") (pinfunction "6_6") (pintype "power_in"))
    )
    (net (code "52") (name "/RESET") (class "Default")
      (node (ref "P1") (pin "3") (pinfunction "3_3") (pintype "passive"))
      (node (ref "P11") (pin "5") (pinfunction "5_5") (pintype "power_in"))
      (node (ref "P13") (pin "6") (pinfunction "6_6") (pintype "passive"))
      (node (ref "P5") (pin "5") (pinfunction "5_5") (pintype "passive"))
      (node (ref "P7") (pin "3") (pinfunction "3_3") (pintype "power_in"))
      (node (ref "SB17") (pin "1") (pinfunction "0_1") (pintype "passive"))
    )
    (net (code "53") (name "/SHIELD_DETECT") (class "Default")
      (node (ref "R39") (pin "1") (pinfunction "1_1") (pintype "passive"))
      (node (ref "SB19") (pin "2") (pinfunction "1_2") (pintype "passive"))
      (node (ref "TP15") (pin "1") (pinfunction "1_1") (pintype "passive"))
    )
    (net (code "54") (name "/SH_GND_DETECT") (class "Default")
      (node (ref "P20") (pin "8") (pinfunction "8_8") (pintype "passive"))
    )
    (net (code "55") (name "/SH_RESET") (class "Default")
      (node (ref "P20") (pin "7") (pinfunction "7_7") (pintype "passive"))
    )
    (net (code "56") (name "/SH_SWDCLK") (class "Default")
      (node (ref "P20") (pin "5") (pinfunction "5_5") (pintype "passive"))
    )
    (net (code "57") (name "/SH_SWDIO") (class "Default")
      (node (ref "P20") (pin "4") (pinfunction "4_4") (pintype "passive"))
    )
    (net (code "58") (name "/SH_SWO") (class "Default")
      (node (ref "P20") (pin "6") (pinfunction "6_6") (pintype "passive"))
    )
    (net (code "59") (name "/SH_VTG") (class "Default")
      (node (ref "P20") (pin "3") (pinfunction "3_3") (pintype "passive"))
    )
    (net (code "60") (name "/SWDCLK") (class "Default")
      (node (ref "P18") (pin "4") (pinfunction "4_4") (pintype "passive+no_connect"))
    )
    (net (code "61") (name "/SWDIO") (class "Default")
      (node (ref "P18") (pin "2") (pinfunction "2_2") (pintype "passive"))
    )
    (net (code "62") (name "GND") (class "Default")
      (node (ref "C19") (pin "1") (pinfunction "1_1") (pintype "passive"))
      (node (ref "C20") (pin "1") (pinfunction "1_1") (pintype "passive"))
      (node (ref "C21") (pin "1") (pinfunction "1_1") (pintype "passive"))
      (node (ref "D2") (pin "1") (pinfunction "GND_1") (pintype "passive"))
      (node (ref "J2") (pin "5") (pinfunction "GND_5") (pintype "power_in"))
      (node (ref "J3") (pin "3") (pinfunction "3_3") (pintype "passive"))
      (node (ref "P1") (pin "6") (pinfunction "6_6") (pintype "passive"))
      (node (ref "P1") (pin "7") (pinfunction "7_7") (pintype "passive"))
      (node (ref "P10") (pin "7") (pinfunction "7_7") (pintype "passive"))
      (node (ref "P13") (pin "1") (pinfunction "1_1") (pintype "passive"))
      (node (ref "P13") (pin "11") (pinfunction "11_11") (pintype "passive"))
      (node (ref "P13") (pin "12") (pinfunction "12_12") (pintype "passive"))
      (node (ref "P13") (pin "13") (pinfunction "13_13") (pintype "passive"))
      (node (ref "P13") (pin "14") (pinfunction "14_14") (pintype "passive"))
      (node (ref "P13") (pin "15") (pinfunction "15_15") (pintype "passive"))
      (node (ref "P13") (pin "3") (pinfunction "3_3") (pintype "passive"))
      (node (ref "P13") (pin "5") (pinfunction "5_5") (pintype "passive"))
      (node (ref "P13") (pin "7") (pinfunction "7_7") (pintype "passive"))
      (node (ref "P13") (pin "9") (pinfunction "9_9") (pintype "passive"))
      (node (ref "P14") (pin "1") (pinfunction "1_1") (pintype "passive"))
      (node (ref "P14") (pin "11") (pinfunction "11_11") (pintype "passive"))
      (node (ref "P14") (pin "3") (pinfunction "3_3") (pintype "passive"))
      (node (ref "P14") (pin "5") (pinfunction "5_5") (pintype "passive"))
      (node (ref "P14") (pin "7") (pinfunction "7_7") (pintype "passive"))
      (node (ref "P14") (pin "9") (pinfunction "9_9") (pintype "passive"))
      (node (ref "P15") (pin "1") (pinfunction "1_1") (pintype "passive"))
      (node (ref "P15") (pin "11") (pinfunction "11_11") (pintype "passive"))
      (node (ref "P15") (pin "13") (pinfunction "13_13") (pintype "passive"))
      (node (ref "P15") (pin "15") (pinfunction "15_15") (pintype "passive"))
      (node (ref "P15") (pin "3") (pinfunction "3_3") (pintype "passive"))
      (node (ref "P15") (pin "5") (pinfunction "5_5") (pintype "passive"))
      (node (ref "P15") (pin "7") (pinfunction "7_7") (pintype "passive"))
      (node (ref "P15") (pin "9") (pinfunction "9_9") (pintype "passive"))
      (node (ref "P16") (pin "1") (pinfunction "1_1") (pintype "passive"))
      (node (ref "P16") (pin "11") (pinfunction "11_11") (pintype "passive"))
      (node (ref "P16") (pin "13") (pinfunction "13_13") (pintype "passive"))
      (node (ref "P16") (pin "14") (pinfunction "14_14") (pintype "passive"))
      (node (ref "P16") (pin "15") (pinfunction "15_15") (pintype "passive"))
      (node (ref "P16") (pin "17") (pinfunction "17_17") (pintype "passive"))
      (node (ref "P16") (pin "19") (pinfunction "19_19") (pintype "passive"))
      (node (ref "P16") (pin "3") (pinfunction "3_3") (pintype "passive"))
      (node (ref "P16") (pin "5") (pinfunction "5_5") (pintype "passive"))
      (node (ref "P16") (pin "7") (pinfunction "7_7") (pintype "passive"))
      (node (ref "P16") (pin "9") (pinfunction "9_9") (pintype "passive"))
      (node (ref "P17") (pin "1") (pinfunction "1_1") (pintype "passive"))
      (node (ref "P17") (pin "11") (pinfunction "11_11") (pintype "passive"))
      (node (ref "P17") (pin "13") (pinfunction "13_13") (pintype "passive"))
      (node (ref "P17") (pin "15") (pinfunction "15_15") (pintype "passive"))
      (node (ref "P17") (pin "17") (pinfunction "17_17") (pintype "passive"))
      (node (ref "P17") (pin "3") (pinfunction "3_3") (pintype "passive"))
      (node (ref "P17") (pin "5") (pinfunction "5_5") (pintype "passive"))
      (node (ref "P17") (pin "7") (pinfunction "7_7") (pintype "passive"))
      (node (ref "P17") (pin "9") (pinfunction "9_9") (pintype "passive"))
      (node (ref "P18") (pin "3") (pinfunction "3_3") (pintype "passive"))
      (node (ref "P18") (pin "5") (pinfunction "5_5") (pintype "passive"))
      (node (ref "P18") (pin "9") (pinfunction "9_9") (pintype "passive"))
      (node (ref "P19") (pin "3") (pinfunction "3_3") (pintype "passive"))
      (node (ref "P19") (pin "5") (pinfunction "5_5") (pintype "passive"))
      (node (ref "P4") (pin "7") (pinfunction "7_7") (pintype "passive"))
      (node (ref "P7") (pin "6") (pinfunction "6_6") (pintype "power_in"))
      (node (ref "P7") (pin "7") (pinfunction "7_7") (pintype "power_in"))
      (node (ref "R12") (pin "1") (pinfunction "1_1") (pintype "passive"))
      (node (ref "R24") (pin "2") (pinfunction "2_2") (pintype "passive"))
      (node (ref "SB18") (pin "1") (pinfunction "0_1") (pintype "passive"))
      (node (ref "TP4") (pin "1") (pinfunction "1_1") (pintype "passive"))
    )
    (net (code "63") (name "Net-(J2-Shield)") (class "Default")
      (node (ref "C19") (pin "2") (pinfunction "2_2") (pintype "passive"))
      (node (ref "J2") (pin "6") (pinfunction "Shield_6") (pintype "power_in"))
      (node (ref "R12") (pin "2") (pinfunction "2_2") (pintype "passive"))
    )
    (net (code "64") (name "Net-(SB18-1)") (class "Default")
      (node (ref "P11") (pin "6") (pinfunction "6_6") (pintype "power_in"))
      (node (ref "P5") (pin "6") (pinfunction "6_6") (pintype "passive"))
      (node (ref "SB18") (pin "2") (pinfunction "1_2") (pintype "passive"))
      (node (ref "SB19") (pin "1") (pinfunction "0_1") (pintype "passive"))
    )
    (net (code "65") (name "V5V") (class "Default")
      (node (ref "J3") (pin "5") (pinfunction "5_5") (pintype "passive"))
      (node (ref "P1") (pin "5") (pinfunction "5_5") (pintype "passive"))
      (node (ref "P11") (pin "2") (pinfunction "2_2") (pintype "passive"))
      (node (ref "P13") (pin "10") (pinfunction "10_10") (pintype "passive"))
      (node (ref "P5") (pin "2") (pinfunction "2_2") (pintype "passive"))
      (node (ref "P7") (pin "5") (pinfunction "5_5") (pintype "power_in"))
    )
    (net (code "66") (name "VBUS") (class "Default")
      (node (ref "C20") (pin "2") (pinfunction "2_2") (pintype "passive"))
      (node (ref "C21") (pin "2") (pinfunction "2_2") (pintype "passive"))
      (node (ref "D2") (pin "4") (pinfunction "VCC_4") (pintype "passive"))
      (node (ref "J2") (pin "1") (pinfunction "VBUS_1") (pintype "power_in"))
      (node (ref "TP3") (pin "1") (pinfunction "1_1") (pintype "passive"))
    )
    (net (code "67") (name "VDD") (class "Default")
      (node (ref "J3") (pin "1") (pinfunction "1_1") (pintype "passive"))
      (node (ref "P1") (pin "1") (pinfunction "1_1") (pintype "passive"))
      (node (ref "P1") (pin "2") (pinfunction "2_2") (pintype "passive"))
      (node (ref "P1") (pin "4") (pinfunction "4_4") (pintype "passive"))
      (node (ref "P13") (pin "2") (pinfunction "2_2") (pintype "passive"))
      (node (ref "P13") (pin "4") (pinfunction "4_4") (pintype "passive"))
      (node (ref "P13") (pin "8") (pinfunction "8_8") (pintype "passive"))
      (node (ref "P18") (pin "1") (pinfunction "1_1") (pintype "passive"))
      (node (ref "P20") (pin "2") (pinfunction "2_2") (pintype "passive"))
      (node (ref "P7") (pin "1") (pinfunction "1_1") (pintype "passive"))
      (node (ref "P7") (pin "2") (pinfunction "2_2") (pintype "passive"))
      (node (ref "P7") (pin "4") (pinfunction "4_4") (pintype "power_in"))
      (node (ref "R21") (pin "2") (pinfunction "2_2") (pintype "passive"))
      (node (ref "R22") (pin "2") (pinfunction "2_2") (pintype "passive"))
      (node (ref "R23") (pin "2") (pinfunction "2_2") (pintype "passive"))
      (node (ref "R39") (pin "2") (pinfunction "2_2") (pintype "passive"))
    )
    (net (code "68") (name "VDD_nRF") (class "Default")
      (node (ref "P20") (pin "1") (pinfunction "1_1") (pintype "passive"))
    )
    (net (code "69") (name "VIN") (class "Default")
      (node (ref "P1") (pin "8") (pinfunction "8_8") (pintype "passive"))
      (node (ref "P13") (pin "16") (pinfunction "16_16") (pintype "passive"))
      (node (ref "P7") (pin "8") (pinfunction "8_8") (pintype "power_in"))
    )
    (net (code "70") (name "unconnected-(J2-ID-Pad4)") (class "Default")
      (node (ref "J2") (pin "4") (pinfunction "ID_4") (pintype "passive"))
    )
    (net (code "71") (name "unconnected-(J3-Pad7)") (class "Default")
      (node (ref "J3") (pin "7") (pinfunction "7_7") (pintype "passive+no_connect"))
    )
    (net (code "72") (name "unconnected-(J3-Pad9)") (class "Default")
      (node (ref "J3") (pin "9") (pinfunction "9_9") (pintype "passive+no_connect"))
    )
    (net (code "73") (name "unconnected-(P18-Pad7)") (class "Default")
      (node (ref "P18") (pin "7") (pinfunction "7_7") (pintype "passive+no_connect"))
    )
    (net (code "74") (name "unconnected-(P18-Pad8)") (class "Default")
      (node (ref "P18") (pin "8") (pinfunction "8_8") (pintype "passive+no_connect"))
    )
    (net (code "75") (name "unconnected-(P19-Pad7)") (class "Default")
      (node (ref "P19") (pin "7") (pinfunction "7_7") (pintype "passive+no_connect"))
    )
    (net (code "76") (name "unconnected-(P19-Pad8)") (class "Default")
      (node (ref "P19") (pin "8") (pinfunction "8_8") (pintype "passive+no_connect"))
    )
  )
)
